# Tracksoar_v2_breakout.net
KiCad netlist of a schematic drawn in EAGLE
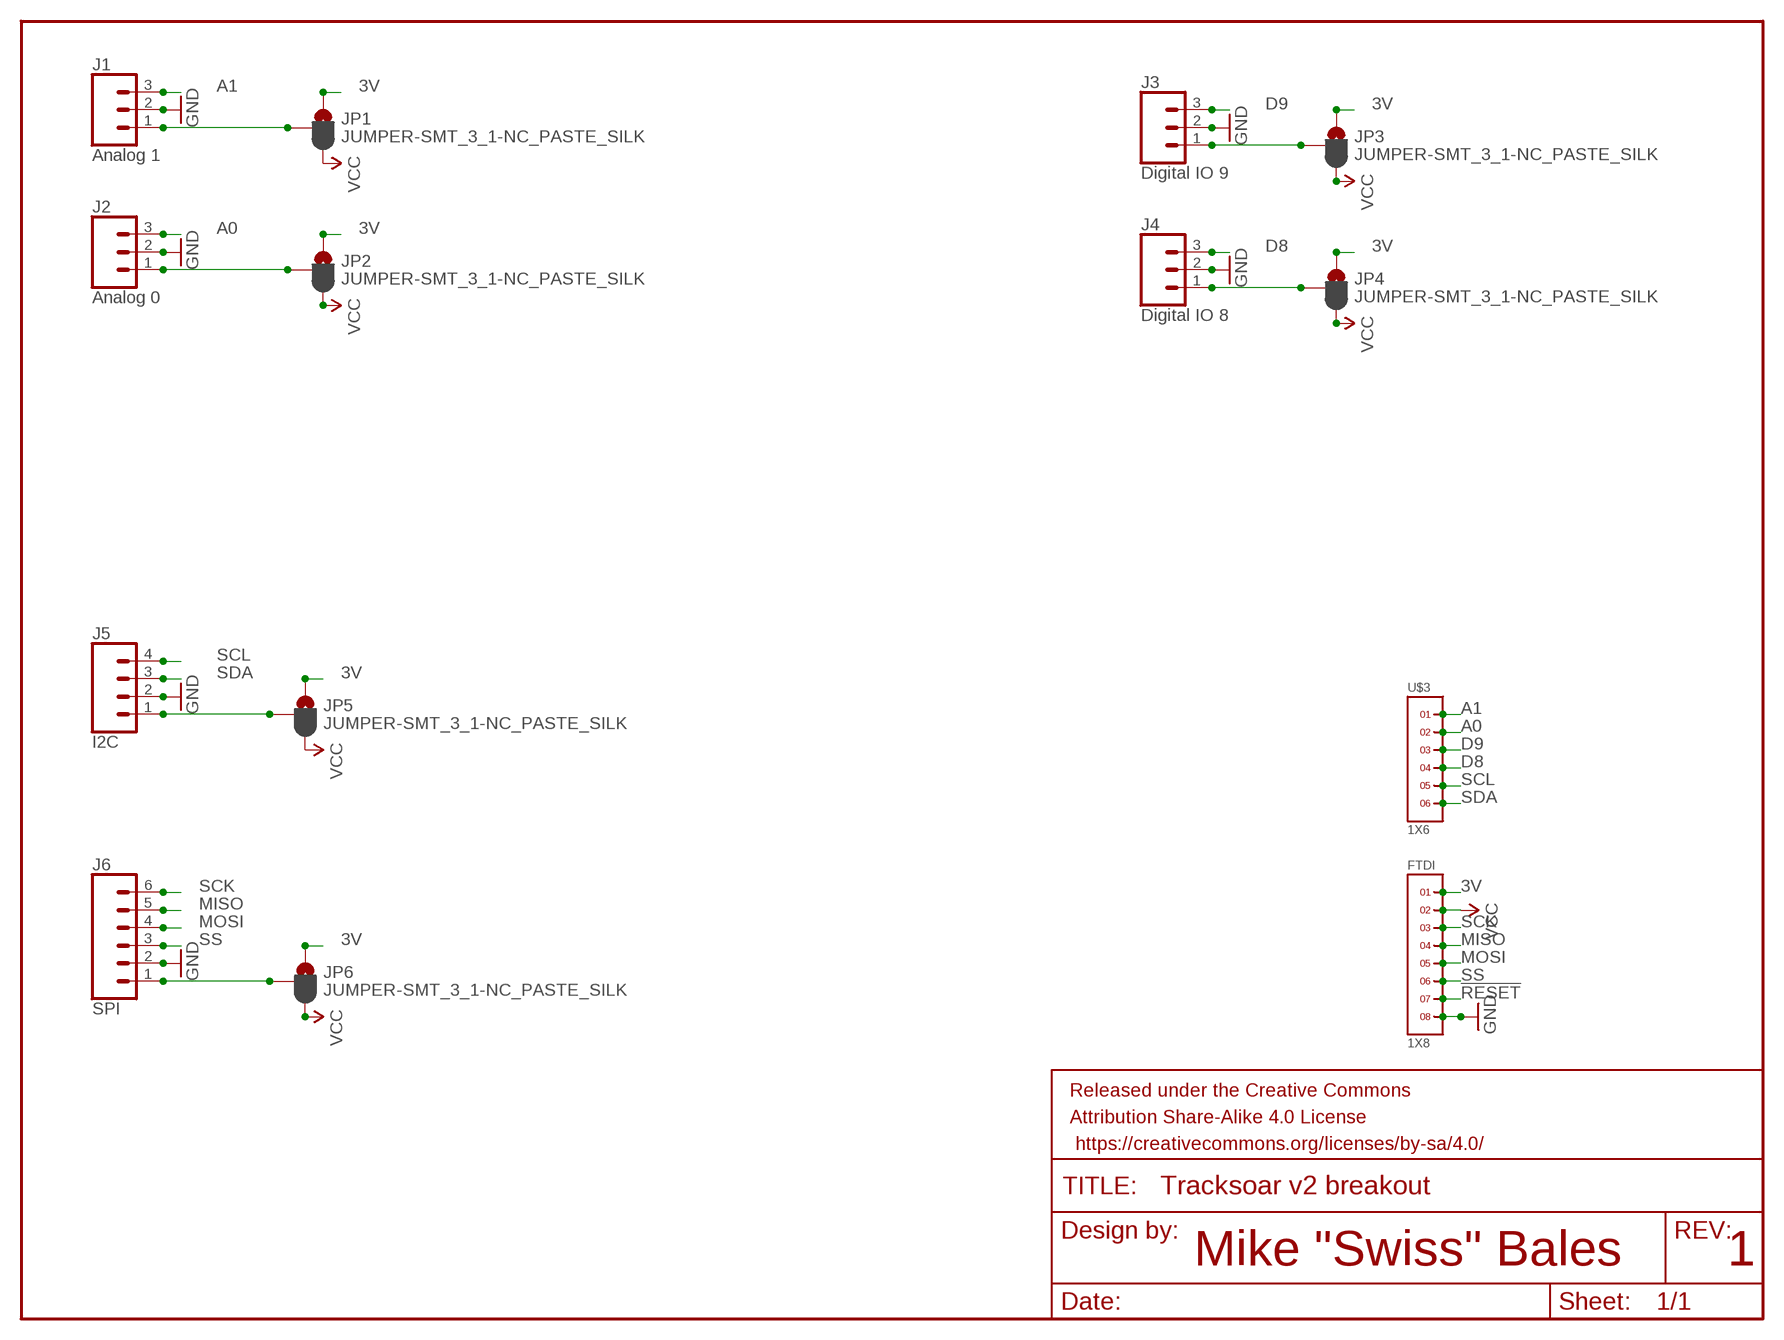
[diagram p0: schematic, sheet 1]

(export (version "E")
  (design (tool "Eeschema 10.0.6"))
  (components
    (comp (ref "FRAME1")
      (value "FRAME-LETTER")
      (footprint "eagle-import:CREATIVE_COMMONS")
      (libsource (lib "eagle-import") (part "FRAME-LETTER"))
    )
    (comp (ref "FTDI")
      (value "1X8")
      (footprint "eagle-import:1X8")
      (libsource (lib "eagle-import") (part "1X8"))
    )
    (comp (ref "J1")
      (value "Analog 1")
      (footprint "eagle-import:1X03_LONGPADS")
      (libsource (lib "eagle-import") (part "CONN_03LONGPADS"))
    )
    (comp (ref "J2")
      (value "Analog 0")
      (footprint "eagle-import:1X03_LONGPADS")
      (libsource (lib "eagle-import") (part "CONN_03LONGPADS"))
    )
    (comp (ref "J3")
      (value "Digital IO 9")
      (footprint "eagle-import:1X03_LONGPADS")
      (libsource (lib "eagle-import") (part "CONN_03LONGPADS"))
    )
    (comp (ref "J4")
      (value "Digital IO 8")
      (footprint "eagle-import:1X03_LONGPADS")
      (libsource (lib "eagle-import") (part "CONN_03LONGPADS"))
    )
    (comp (ref "J5")
      (value "I2C")
      (footprint "eagle-import:1X04_LONGPADS")
      (libsource (lib "eagle-import") (part "CONN_04LONGPADS"))
    )
    (comp (ref "J6")
      (value "SPI")
      (footprint "eagle-import:1X06_LONGPADS")
      (libsource (lib "eagle-import") (part "CONN_06LONGPADS"))
    )
    (comp (ref "JP1")
      (value "JUMPER-SMT_3_1-NC_PASTE_SILK")
      (footprint "eagle-import:SMT-JUMPER_3_1-NC_PASTE_SILK")
      (libsource (lib "eagle-import") (part "JUMPER-SMT_3_1-NC_PASTE_SILK"))
    )
    (comp (ref "JP2")
      (value "JUMPER-SMT_3_1-NC_PASTE_SILK")
      (footprint "eagle-import:SMT-JUMPER_3_1-NC_PASTE_SILK")
      (libsource (lib "eagle-import") (part "JUMPER-SMT_3_1-NC_PASTE_SILK"))
    )
    (comp (ref "JP3")
      (value "JUMPER-SMT_3_1-NC_PASTE_SILK")
      (footprint "eagle-import:SMT-JUMPER_3_1-NC_PASTE_SILK")
      (libsource (lib "eagle-import") (part "JUMPER-SMT_3_1-NC_PASTE_SILK"))
    )
    (comp (ref "JP4")
      (value "JUMPER-SMT_3_1-NC_PASTE_SILK")
      (footprint "eagle-import:SMT-JUMPER_3_1-NC_PASTE_SILK")
      (libsource (lib "eagle-import") (part "JUMPER-SMT_3_1-NC_PASTE_SILK"))
    )
    (comp (ref "JP5")
      (value "JUMPER-SMT_3_1-NC_PASTE_SILK")
      (footprint "eagle-import:SMT-JUMPER_3_1-NC_PASTE_SILK")
      (libsource (lib "eagle-import") (part "JUMPER-SMT_3_1-NC_PASTE_SILK"))
    )
    (comp (ref "JP6")
      (value "JUMPER-SMT_3_1-NC_PASTE_SILK")
      (footprint "eagle-import:SMT-JUMPER_3_1-NC_PASTE_SILK")
      (libsource (lib "eagle-import") (part "JUMPER-SMT_3_1-NC_PASTE_SILK"))
    )
    (comp (ref "U$3")
      (value "1X6")
      (footprint "eagle-import:1X6")
      (libsource (lib "eagle-import") (part "1X6"))
    )
  )
  (nets
    (net (code "1") (name "/3V") (class "Default")
      (node (ref "FTDI") (pin "1") (pinfunction "1_1") (pintype "bidirectional"))
      (node (ref "JP1") (pin "1") (pinfunction "1_1") (pintype "passive"))
      (node (ref "JP2") (pin "1") (pinfunction "1_1") (pintype "passive"))
      (node (ref "JP3") (pin "1") (pinfunction "1_1") (pintype "passive"))
      (node (ref "JP4") (pin "1") (pinfunction "1_1") (pintype "passive"))
      (node (ref "JP5") (pin "1") (pinfunction "1_1") (pintype "passive"))
      (node (ref "JP6") (pin "1") (pinfunction "1_1") (pintype "passive"))
    )
    (net (code "2") (name "/A0") (class "Default")
      (node (ref "J2") (pin "3") (pinfunction "3_3") (pintype "passive"))
      (node (ref "U$3") (pin "2") (pinfunction "2_2") (pintype "bidirectional"))
    )
    (net (code "3") (name "/A1") (class "Default")
      (node (ref "J1") (pin "3") (pinfunction "3_3") (pintype "passive"))
      (node (ref "U$3") (pin "1") (pinfunction "1_1") (pintype "bidirectional"))
    )
    (net (code "4") (name "/D8") (class "Default")
      (node (ref "J4") (pin "3") (pinfunction "3_3") (pintype "passive"))
      (node (ref "U$3") (pin "4") (pinfunction "4_4") (pintype "bidirectional"))
    )
    (net (code "5") (name "/D9") (class "Default")
      (node (ref "J3") (pin "3") (pinfunction "3_3") (pintype "passive"))
      (node (ref "U$3") (pin "3") (pinfunction "3_3") (pintype "bidirectional"))
    )
    (net (code "6") (name "/MISO") (class "Default")
      (node (ref "FTDI") (pin "4") (pinfunction "4_4") (pintype "bidirectional"))
      (node (ref "J6") (pin "5") (pinfunction "5_5") (pintype "passive"))
    )
    (net (code "7") (name "/MOSI") (class "Default")
      (node (ref "FTDI") (pin "5") (pinfunction "5_5") (pintype "bidirectional"))
      (node (ref "J6") (pin "4") (pinfunction "4_4") (pintype "passive"))
    )
    (net (code "8") (name "/SCK") (class "Default")
      (node (ref "FTDI") (pin "3") (pinfunction "3_3") (pintype "bidirectional"))
      (node (ref "J6") (pin "6") (pinfunction "6_6") (pintype "passive"))
    )
    (net (code "9") (name "/SCL") (class "Default")
      (node (ref "J5") (pin "4") (pinfunction "4_4") (pintype "passive"))
      (node (ref "U$3") (pin "5") (pinfunction "5_5") (pintype "bidirectional"))
    )
    (net (code "10") (name "/SDA") (class "Default")
      (node (ref "J5") (pin "3") (pinfunction "3_3") (pintype "passive"))
      (node (ref "U$3") (pin "6") (pinfunction "6_6") (pintype "bidirectional"))
    )
    (net (code "11") (name "/SS") (class "Default")
      (node (ref "FTDI") (pin "6") (pinfunction "6_6") (pintype "bidirectional"))
      (node (ref "J6") (pin "3") (pinfunction "3_3") (pintype "passive"))
    )
    (net (code "12") (name "/~{RESET}") (class "Default")
      (node (ref "FTDI") (pin "7") (pinfunction "7_7") (pintype "bidirectional"))
    )
    (net (code "13") (name "GND") (class "Default")
      (node (ref "FTDI") (pin "8") (pinfunction "8_8") (pintype "bidirectional"))
      (node (ref "J1") (pin "2") (pinfunction "2_2") (pintype "passive"))
      (node (ref "J2") (pin "2") (pinfunction "2_2") (pintype "passive"))
      (node (ref "J3") (pin "2") (pinfunction "2_2") (pintype "passive"))
      (node (ref "J4") (pin "2") (pinfunction "2_2") (pintype "passive"))
      (node (ref "J5") (pin "2") (pinfunction "2_2") (pintype "passive"))
      (node (ref "J6") (pin "2") (pinfunction "2_2") (pintype "passive"))
    )
    (net (code "14") (name "Net-(J1-Pad1)") (class "Default")
      (node (ref "J1") (pin "1") (pinfunction "1_1") (pintype "passive"))
      (node (ref "JP1") (pin "2") (pinfunction "2_2") (pintype "passive"))
    )
    (net (code "15") (name "Net-(J2-Pad1)") (class "Default")
      (node (ref "J2") (pin "1") (pinfunction "1_1") (pintype "passive"))
      (node (ref "JP2") (pin "2") (pinfunction "2_2") (pintype "passive"))
    )
    (net (code "16") (name "Net-(J3-Pad1)") (class "Default")
      (node (ref "J3") (pin "1") (pinfunction "1_1") (pintype "passive"))
      (node (ref "JP3") (pin "2") (pinfunction "2_2") (pintype "passive"))
    )
    (net (code "17") (name "Net-(J4-Pad1)") (class "Default")
      (node (ref "J4") (pin "1") (pinfunction "1_1") (pintype "passive"))
      (node (ref "JP4") (pin "2") (pinfunction "2_2") (pintype "passive"))
    )
    (net (code "18") (name "Net-(J5-Pad1)") (class "Default")
      (node (ref "J5") (pin "1") (pinfunction "1_1") (pintype "passive"))
      (node (ref "JP5") (pin "2") (pinfunction "2_2") (pintype "passive"))
    )
    (net (code "19") (name "Net-(J6-Pad1)") (class "Default")
      (node (ref "J6") (pin "1") (pinfunction "1_1") (pintype "passive"))
      (node (ref "JP6") (pin "2") (pinfunction "2_2") (pintype "passive"))
    )
    (net (code "20") (name "VCC") (class "Default")
      (node (ref "FTDI") (pin "2") (pinfunction "2_2") (pintype "bidirectional"))
      (node (ref "JP1") (pin "3") (pinfunction "3_3") (pintype "passive"))
      (node (ref "JP2") (pin "3") (pinfunction "3_3") (pintype "passive"))
      (node (ref "JP3") (pin "3") (pinfunction "3_3") (pintype "passive"))
      (node (ref "JP4") (pin "3") (pinfunction "3_3") (pintype "passive"))
      (node (ref "JP5") (pin "3") (pinfunction "3_3") (pintype "passive"))
      (node (ref "JP6") (pin "3") (pinfunction "3_3") (pintype "passive"))
    )
  )
)
